# controller.net
KiCad netlist of a schematic drawn in EAGLE
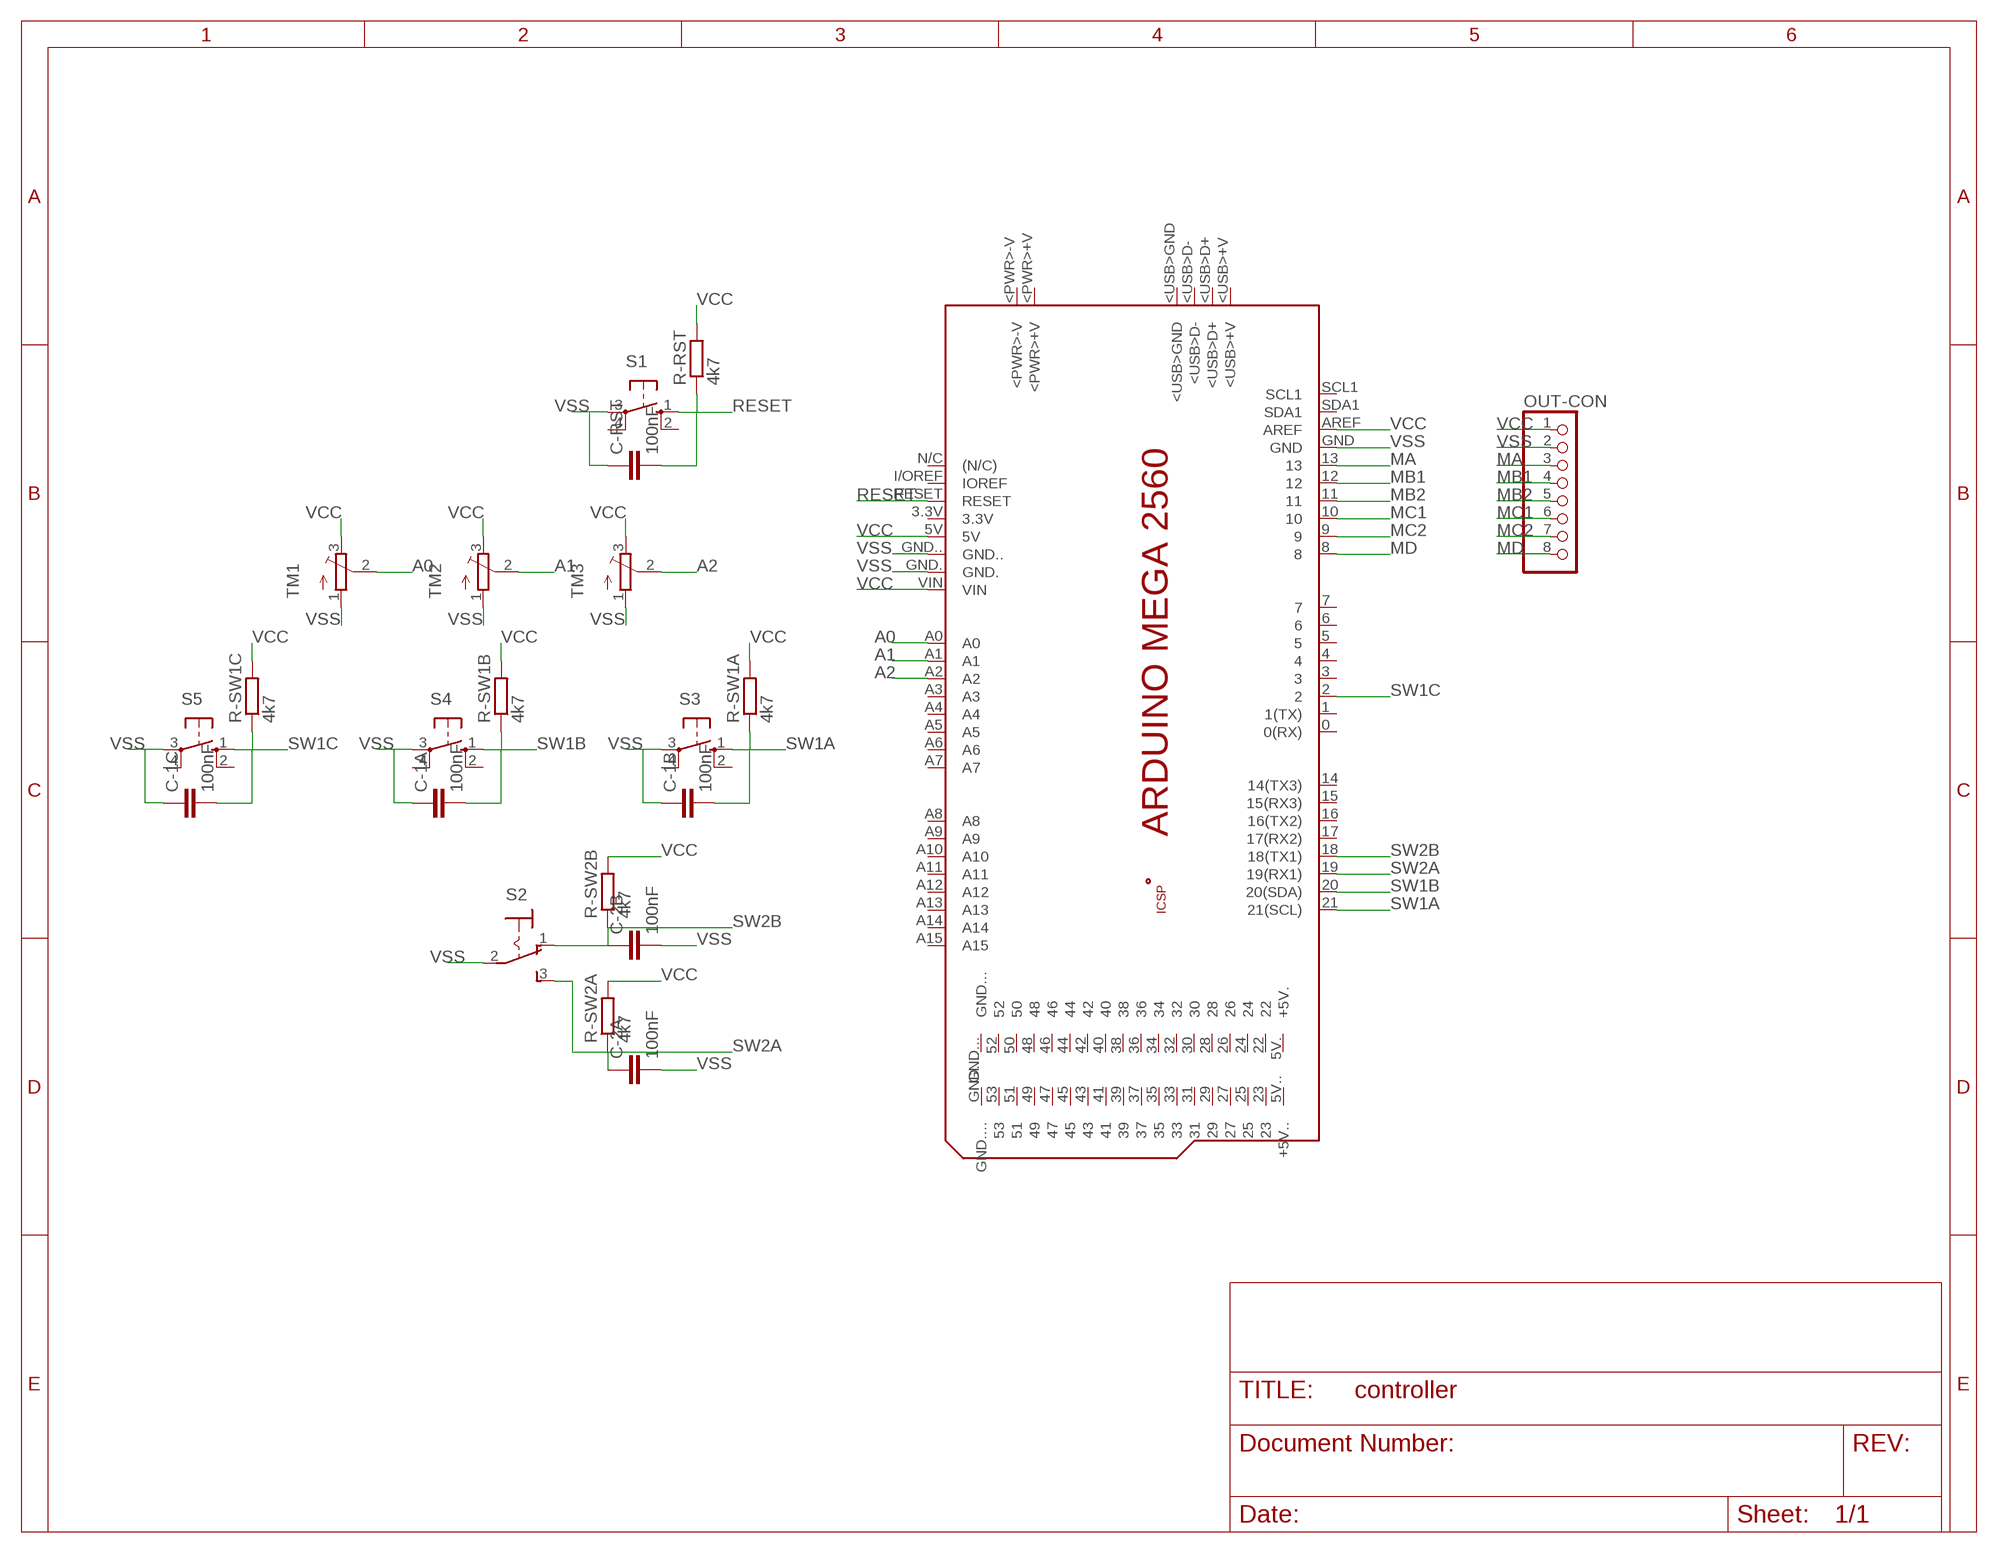
[diagram p0: schematic, sheet 1]

(export (version "E")
  (design (tool "Eeschema 10.0.6"))
  (components
    (comp (ref "C-1A")
      (value "100nF")
      (footprint "eagle-import:C025-024X044")
      (libsource (lib "eagle-import") (part "C-EU025-024X044"))
    )
    (comp (ref "C-1B")
      (value "100nF")
      (footprint "eagle-import:C025-024X044")
      (libsource (lib "eagle-import") (part "C-EU025-024X044"))
    )
    (comp (ref "C-1C")
      (value "100nF")
      (footprint "eagle-import:C025-024X044")
      (libsource (lib "eagle-import") (part "C-EU025-024X044"))
    )
    (comp (ref "C-2A")
      (value "100nF")
      (footprint "eagle-import:C025-024X044")
      (libsource (lib "eagle-import") (part "C-EU025-024X044"))
    )
    (comp (ref "C-2B")
      (value "100nF")
      (footprint "eagle-import:C025-024X044")
      (libsource (lib "eagle-import") (part "C-EU025-024X044"))
    )
    (comp (ref "C-RST")
      (value "100nF")
      (footprint "eagle-import:C025-024X044")
      (libsource (lib "eagle-import") (part "C-EU025-024X044"))
    )
    (comp (ref "OUT-CON")
      (value "PINHD-1X8")
      (footprint "eagle-import:1X08")
      (libsource (lib "eagle-import") (part "PINHD-1X8"))
    )
    (comp (ref "PCB1")
      (value "ARDUINO_MEGA2560")
      (footprint "eagle-import:ARDUINO_MEGA2560")
      (libsource (lib "eagle-import") (part "ARDUINO_MEGA2560"))
    )
    (comp (ref "R-RST")
      (value "4k7")
      (footprint "eagle-import:0204_7")
      (libsource (lib "eagle-import") (part "R-EU_0204/7"))
    )
    (comp (ref "R-SW1A")
      (value "4k7")
      (footprint "eagle-import:0204_7")
      (libsource (lib "eagle-import") (part "R-EU_0204/7"))
    )
    (comp (ref "R-SW1B")
      (value "4k7")
      (footprint "eagle-import:0204_7")
      (libsource (lib "eagle-import") (part "R-EU_0204/7"))
    )
    (comp (ref "R-SW1C")
      (value "4k7")
      (footprint "eagle-import:0204_7")
      (libsource (lib "eagle-import") (part "R-EU_0204/7"))
    )
    (comp (ref "R-SW2A")
      (value "4k7")
      (footprint "eagle-import:0204_7")
      (libsource (lib "eagle-import") (part "R-EU_0204/7"))
    )
    (comp (ref "R-SW2B")
      (value "4k7")
      (footprint "eagle-import:0204_7")
      (libsource (lib "eagle-import") (part "R-EU_0204/7"))
    )
    (comp (ref "S1")
      (value "10-XX")
      (footprint "eagle-import:B3F-10XX")
      (fields (field (name "MPN") "B3F-1000"))
      (libsource (lib "eagle-import") (part "10-XX"))
    )
    (comp (ref "S2")
      (value "M9040P")
      (footprint "eagle-import:M9040P")
      (libsource (lib "eagle-import") (part "M9040P"))
    )
    (comp (ref "S3")
      (value "10-XX")
      (footprint "eagle-import:B3F-10XX")
      (fields (field (name "MPN") "B3F-1000"))
      (libsource (lib "eagle-import") (part "10-XX"))
    )
    (comp (ref "S4")
      (value "10-XX")
      (footprint "eagle-import:B3F-10XX")
      (fields (field (name "MPN") "B3F-1000"))
      (libsource (lib "eagle-import") (part "10-XX"))
    )
    (comp (ref "S5")
      (value "10-XX")
      (footprint "eagle-import:B3F-10XX")
      (fields (field (name "MPN") "B3F-1000"))
      (libsource (lib "eagle-import") (part "10-XX"))
    )
    (comp (ref "TM1")
      (value "TRIMPOT3386")
      (footprint "eagle-import:TRIM-3386")
      (libsource (lib "eagle-import") (part "TRIMPOT3386"))
    )
    (comp (ref "TM2")
      (value "TRIMPOT3386")
      (footprint "eagle-import:TRIM-3386")
      (libsource (lib "eagle-import") (part "TRIMPOT3386"))
    )
    (comp (ref "TM3")
      (value "TRIMPOT3386")
      (footprint "eagle-import:TRIM-3386")
      (libsource (lib "eagle-import") (part "TRIMPOT3386"))
    )
  )
  (nets
    (net (code "1") (name "/A0") (class "Default")
      (node (ref "PCB1") (pin "A0") (pinfunction "A0_A0") (pintype "bidirectional"))
      (node (ref "TM1") (pin "2") (pinfunction "S_2") (pintype "passive"))
    )
    (net (code "2") (name "/A1") (class "Default")
      (node (ref "PCB1") (pin "A1") (pinfunction "A1_A1") (pintype "bidirectional"))
      (node (ref "TM2") (pin "2") (pinfunction "S_2") (pintype "passive"))
    )
    (net (code "3") (name "/A2") (class "Default")
      (node (ref "PCB1") (pin "A2") (pinfunction "A2_A2") (pintype "bidirectional"))
      (node (ref "TM3") (pin "2") (pinfunction "S_2") (pintype "passive"))
    )
    (net (code "4") (name "/MA") (class "Default")
      (node (ref "OUT-CON") (pin "3") (pinfunction "3_3") (pintype "passive"))
      (node (ref "PCB1") (pin "13") (pinfunction "13_13") (pintype "bidirectional"))
    )
    (net (code "5") (name "/MB1") (class "Default")
      (node (ref "OUT-CON") (pin "4") (pinfunction "4_4") (pintype "passive"))
      (node (ref "PCB1") (pin "12") (pinfunction "12_12") (pintype "bidirectional"))
    )
    (net (code "6") (name "/MB2") (class "Default")
      (node (ref "OUT-CON") (pin "5") (pinfunction "5_5") (pintype "passive"))
      (node (ref "PCB1") (pin "11") (pinfunction "11_11") (pintype "bidirectional"))
    )
    (net (code "7") (name "/MC1") (class "Default")
      (node (ref "OUT-CON") (pin "6") (pinfunction "6_6") (pintype "passive"))
      (node (ref "PCB1") (pin "10") (pinfunction "10_10") (pintype "bidirectional"))
    )
    (net (code "8") (name "/MC2") (class "Default")
      (node (ref "OUT-CON") (pin "7") (pinfunction "7_7") (pintype "passive"))
      (node (ref "PCB1") (pin "9") (pinfunction "9_9") (pintype "bidirectional"))
    )
    (net (code "9") (name "/MD") (class "Default")
      (node (ref "OUT-CON") (pin "8") (pinfunction "8_8") (pintype "passive"))
      (node (ref "PCB1") (pin "8") (pinfunction "8_8") (pintype "bidirectional"))
    )
    (net (code "10") (name "/RESET") (class "Default")
      (node (ref "C-RST") (pin "2") (pinfunction "2_2") (pintype "passive"))
      (node (ref "PCB1") (pin "RESET") (pinfunction "RESET_RESET") (pintype "bidirectional"))
      (node (ref "R-RST") (pin "1") (pinfunction "1_1") (pintype "passive"))
      (node (ref "S1") (pin "1") (pinfunction "S_1") (pintype "passive"))
    )
    (net (code "11") (name "/SW1A") (class "Default")
      (node (ref "C-1B") (pin "2") (pinfunction "2_2") (pintype "passive"))
      (node (ref "PCB1") (pin "21") (pinfunction "21(SCL)_21") (pintype "bidirectional"))
      (node (ref "R-SW1A") (pin "1") (pinfunction "1_1") (pintype "passive"))
      (node (ref "S3") (pin "1") (pinfunction "S_1") (pintype "passive"))
    )
    (net (code "12") (name "/SW1B") (class "Default")
      (node (ref "C-1A") (pin "2") (pinfunction "2_2") (pintype "passive"))
      (node (ref "PCB1") (pin "20") (pinfunction "20(SDA)_20") (pintype "bidirectional"))
      (node (ref "R-SW1B") (pin "1") (pinfunction "1_1") (pintype "passive"))
      (node (ref "S4") (pin "1") (pinfunction "S_1") (pintype "passive"))
    )
    (net (code "13") (name "/SW1C") (class "Default")
      (node (ref "C-1C") (pin "2") (pinfunction "2_2") (pintype "passive"))
      (node (ref "PCB1") (pin "2") (pinfunction "2_2") (pintype "bidirectional"))
      (node (ref "R-SW1C") (pin "1") (pinfunction "1_1") (pintype "passive"))
      (node (ref "S5") (pin "1") (pinfunction "S_1") (pintype "passive"))
    )
    (net (code "14") (name "/SW2A") (class "Default")
      (node (ref "C-2A") (pin "1") (pinfunction "1_1") (pintype "passive"))
      (node (ref "PCB1") (pin "19") (pinfunction "19(RX1)_19") (pintype "bidirectional"))
      (node (ref "R-SW2A") (pin "1") (pinfunction "1_1") (pintype "passive"))
      (node (ref "S2") (pin "3") (pinfunction "S_3") (pintype "passive"))
    )
    (net (code "15") (name "/SW2B") (class "Default")
      (node (ref "C-2B") (pin "1") (pinfunction "1_1") (pintype "passive"))
      (node (ref "PCB1") (pin "18") (pinfunction "18(TX1)_18") (pintype "bidirectional"))
      (node (ref "R-SW2B") (pin "1") (pinfunction "1_1") (pintype "passive"))
      (node (ref "S2") (pin "1") (pinfunction "O_1") (pintype "passive"))
    )
    (net (code "16") (name "/VCC") (class "Default")
      (node (ref "OUT-CON") (pin "1") (pinfunction "1_1") (pintype "passive"))
      (node (ref "PCB1") (pin "5V") (pinfunction "5V_5V") (pintype "bidirectional"))
      (node (ref "PCB1") (pin "AREF") (pinfunction "AREF_AREF") (pintype "bidirectional"))
      (node (ref "PCB1") (pin "VIN") (pinfunction "VIN_VIN") (pintype "bidirectional"))
      (node (ref "R-RST") (pin "2") (pinfunction "2_2") (pintype "passive"))
      (node (ref "R-SW1A") (pin "2") (pinfunction "2_2") (pintype "passive"))
      (node (ref "R-SW1B") (pin "2") (pinfunction "2_2") (pintype "passive"))
      (node (ref "R-SW1C") (pin "2") (pinfunction "2_2") (pintype "passive"))
      (node (ref "R-SW2A") (pin "2") (pinfunction "2_2") (pintype "passive"))
      (node (ref "R-SW2B") (pin "2") (pinfunction "2_2") (pintype "passive"))
      (node (ref "TM1") (pin "3") (pinfunction "E_3") (pintype "passive"))
      (node (ref "TM2") (pin "3") (pinfunction "E_3") (pintype "passive"))
      (node (ref "TM3") (pin "3") (pinfunction "E_3") (pintype "passive"))
    )
    (net (code "17") (name "/VSS") (class "Default")
      (node (ref "C-1A") (pin "1") (pinfunction "1_1") (pintype "passive"))
      (node (ref "C-1B") (pin "1") (pinfunction "1_1") (pintype "passive"))
      (node (ref "C-1C") (pin "1") (pinfunction "1_1") (pintype "passive"))
      (node (ref "C-2A") (pin "2") (pinfunction "2_2") (pintype "passive"))
      (node (ref "C-2B") (pin "2") (pinfunction "2_2") (pintype "passive"))
      (node (ref "C-RST") (pin "1") (pinfunction "1_1") (pintype "passive"))
      (node (ref "OUT-CON") (pin "2") (pinfunction "2_2") (pintype "passive"))
      (node (ref "PCB1") (pin "GND") (pinfunction "GND_GND") (pintype "bidirectional"))
      (node (ref "PCB1") (pin "GND.") (pinfunction "GND._GND.") (pintype "bidirectional"))
      (node (ref "PCB1") (pin "GND..") (pinfunction "GND.._GND..") (pintype "bidirectional"))
      (node (ref "S1") (pin "3") (pinfunction "P_3") (pintype "passive"))
      (node (ref "S2") (pin "2") (pinfunction "P_2") (pintype "passive"))
      (node (ref "S3") (pin "3") (pinfunction "P_3") (pintype "passive"))
      (node (ref "S4") (pin "3") (pinfunction "P_3") (pintype "passive"))
      (node (ref "S5") (pin "3") (pinfunction "P_3") (pintype "passive"))
      (node (ref "TM1") (pin "1") (pinfunction "A_1") (pintype "passive"))
      (node (ref "TM2") (pin "1") (pinfunction "A_1") (pintype "passive"))
      (node (ref "TM3") (pin "1") (pinfunction "A_1") (pintype "passive"))
    )
    (net (code "18") (name "unconnected-(PCB1-(N{slash}C)-PadN{slash}C)") (class "Default")
      (node (ref "PCB1") (pin "N/C") (pinfunction "(N/C)_N/C") (pintype "bidirectional"))
    )
    (net (code "19") (name "unconnected-(PCB1-+5V.-Pad5V.)") (class "Default")
      (node (ref "PCB1") (pin "5V.") (pinfunction "+5V._5V.") (pintype "bidirectional"))
    )
    (net (code "20") (name "unconnected-(PCB1-+5V..-Pad5V..)") (class "Default")
      (node (ref "PCB1") (pin "5V..") (pinfunction "+5V.._5V..") (pintype "bidirectional"))
    )
    (net (code "21") (name "unconnected-(PCB1-0(RX)-Pad0)") (class "Default")
      (node (ref "PCB1") (pin "0") (pinfunction "0(RX)_0") (pintype "bidirectional"))
    )
    (net (code "22") (name "unconnected-(PCB1-1(TX)-Pad1)") (class "Default")
      (node (ref "PCB1") (pin "1") (pinfunction "1(TX)_1") (pintype "bidirectional"))
    )
    (net (code "23") (name "unconnected-(PCB1-14(TX3)-Pad14)") (class "Default")
      (node (ref "PCB1") (pin "14") (pinfunction "14(TX3)_14") (pintype "bidirectional"))
    )
    (net (code "24") (name "unconnected-(PCB1-15(RX3)-Pad15)") (class "Default")
      (node (ref "PCB1") (pin "15") (pinfunction "15(RX3)_15") (pintype "bidirectional"))
    )
    (net (code "25") (name "unconnected-(PCB1-16(TX2)-Pad16)") (class "Default")
      (node (ref "PCB1") (pin "16") (pinfunction "16(TX2)_16") (pintype "bidirectional"))
    )
    (net (code "26") (name "unconnected-(PCB1-17(RX2)-Pad17)") (class "Default")
      (node (ref "PCB1") (pin "17") (pinfunction "17(RX2)_17") (pintype "bidirectional"))
    )
    (net (code "27") (name "unconnected-(PCB1-IOREF-PadI{slash}OREF)") (class "Default")
      (node (ref "PCB1") (pin "I/OREF") (pinfunction "IOREF_I/OREF") (pintype "bidirectional"))
    )
    (net (code "28") (name "unconnected-(PCB1-Pad+5V_)") (class "Default")
      (node (ref "PCB1") (pin "+5V_") (pinfunction "+5V__+5V_") (pintype "bidirectional"))
    )
    (net (code "29") (name "unconnected-(PCB1-Pad3)") (class "Default")
      (node (ref "PCB1") (pin "3") (pinfunction "3_3") (pintype "bidirectional"))
    )
    (net (code "30") (name "unconnected-(PCB1-Pad3.3V)") (class "Default")
      (node (ref "PCB1") (pin "3.3V") (pinfunction "3.3V_3.3V") (pintype "bidirectional"))
    )
    (net (code "31") (name "unconnected-(PCB1-Pad4)") (class "Default")
      (node (ref "PCB1") (pin "4") (pinfunction "4_4") (pintype "bidirectional"))
    )
    (net (code "32") (name "unconnected-(PCB1-Pad5)") (class "Default")
      (node (ref "PCB1") (pin "5") (pinfunction "5_5") (pintype "bidirectional"))
    )
    (net (code "33") (name "unconnected-(PCB1-Pad6)") (class "Default")
      (node (ref "PCB1") (pin "6") (pinfunction "6_6") (pintype "bidirectional"))
    )
    (net (code "34") (name "unconnected-(PCB1-Pad7)") (class "Default")
      (node (ref "PCB1") (pin "7") (pinfunction "7_7") (pintype "bidirectional"))
    )
    (net (code "35") (name "unconnected-(PCB1-Pad22)") (class "Default")
      (node (ref "PCB1") (pin "22") (pinfunction "22_22") (pintype "bidirectional"))
    )
    (net (code "36") (name "unconnected-(PCB1-Pad23)") (class "Default")
      (node (ref "PCB1") (pin "23") (pinfunction "23_23") (pintype "bidirectional"))
    )
    (net (code "37") (name "unconnected-(PCB1-Pad24)") (class "Default")
      (node (ref "PCB1") (pin "24") (pinfunction "24_24") (pintype "bidirectional"))
    )
    (net (code "38") (name "unconnected-(PCB1-Pad25)") (class "Default")
      (node (ref "PCB1") (pin "25") (pinfunction "25_25") (pintype "bidirectional"))
    )
    (net (code "39") (name "unconnected-(PCB1-Pad26)") (class "Default")
      (node (ref "PCB1") (pin "26") (pinfunction "26_26") (pintype "bidirectional"))
    )
    (net (code "40") (name "unconnected-(PCB1-Pad27)") (class "Default")
      (node (ref "PCB1") (pin "27") (pinfunction "27_27") (pintype "bidirectional"))
    )
    (net (code "41") (name "unconnected-(PCB1-Pad28)") (class "Default")
      (node (ref "PCB1") (pin "28") (pinfunction "28_28") (pintype "bidirectional"))
    )
    (net (code "42") (name "unconnected-(PCB1-Pad29)") (class "Default")
      (node (ref "PCB1") (pin "29") (pinfunction "29_29") (pintype "bidirectional"))
    )
    (net (code "43") (name "unconnected-(PCB1-Pad30)") (class "Default")
      (node (ref "PCB1") (pin "30") (pinfunction "30_30") (pintype "bidirectional"))
    )
    (net (code "44") (name "unconnected-(PCB1-Pad31)") (class "Default")
      (node (ref "PCB1") (pin "31") (pinfunction "31_31") (pintype "bidirectional"))
    )
    (net (code "45") (name "unconnected-(PCB1-Pad32)") (class "Default")
      (node (ref "PCB1") (pin "32") (pinfunction "32_32") (pintype "bidirectional"))
    )
    (net (code "46") (name "unconnected-(PCB1-Pad33)") (class "Default")
      (node (ref "PCB1") (pin "33") (pinfunction "33_33") (pintype "bidirectional"))
    )
    (net (code "47") (name "unconnected-(PCB1-Pad34)") (class "Default")
      (node (ref "PCB1") (pin "34") (pinfunction "34_34") (pintype "bidirectional"))
    )
    (net (code "48") (name "unconnected-(PCB1-Pad35)") (class "Default")
      (node (ref "PCB1") (pin "35") (pinfunction "35_35") (pintype "bidirectional"))
    )
    (net (code "49") (name "unconnected-(PCB1-Pad36)") (class "Default")
      (node (ref "PCB1") (pin "36") (pinfunction "36_36") (pintype "bidirectional"))
    )
    (net (code "50") (name "unconnected-(PCB1-Pad37)") (class "Default")
      (node (ref "PCB1") (pin "37") (pinfunction "37_37") (pintype "bidirectional"))
    )
    (net (code "51") (name "unconnected-(PCB1-Pad38)") (class "Default")
      (node (ref "PCB1") (pin "38") (pinfunction "38_38") (pintype "bidirectional"))
    )
    (net (code "52") (name "unconnected-(PCB1-Pad39)") (class "Default")
      (node (ref "PCB1") (pin "39") (pinfunction "39_39") (pintype "bidirectional"))
    )
    (net (code "53") (name "unconnected-(PCB1-Pad40)") (class "Default")
      (node (ref "PCB1") (pin "40") (pinfunction "40_40") (pintype "bidirectional"))
    )
    (net (code "54") (name "unconnected-(PCB1-Pad41)") (class "Default")
      (node (ref "PCB1") (pin "41") (pinfunction "41_41") (pintype "bidirectional"))
    )
    (net (code "55") (name "unconnected-(PCB1-Pad42)") (class "Default")
      (node (ref "PCB1") (pin "42") (pinfunction "42_42") (pintype "bidirectional"))
    )
    (net (code "56") (name "unconnected-(PCB1-Pad43)") (class "Default")
      (node (ref "PCB1") (pin "43") (pinfunction "43_43") (pintype "bidirectional"))
    )
    (net (code "57") (name "unconnected-(PCB1-Pad44)") (class "Default")
      (node (ref "PCB1") (pin "44") (pinfunction "44_44") (pintype "bidirectional"))
    )
    (net (code "58") (name "unconnected-(PCB1-Pad45)") (class "Default")
      (node (ref "PCB1") (pin "45") (pinfunction "45_45") (pintype "bidirectional"))
    )
    (net (code "59") (name "unconnected-(PCB1-Pad46)") (class "Default")
      (node (ref "PCB1") (pin "46") (pinfunction "46_46") (pintype "bidirectional"))
    )
    (net (code "60") (name "unconnected-(PCB1-Pad47)") (class "Default")
      (node (ref "PCB1") (pin "47") (pinfunction "47_47") (pintype "bidirectional"))
    )
    (net (code "61") (name "unconnected-(PCB1-Pad48)") (class "Default")
      (node (ref "PCB1") (pin "48") (pinfunction "48_48") (pintype "bidirectional"))
    )
    (net (code "62") (name "unconnected-(PCB1-Pad49)") (class "Default")
      (node (ref "PCB1") (pin "49") (pinfunction "49_49") (pintype "bidirectional"))
    )
    (net (code "63") (name "unconnected-(PCB1-Pad50)") (class "Default")
      (node (ref "PCB1") (pin "50") (pinfunction "50_50") (pintype "bidirectional"))
    )
    (net (code "64") (name "unconnected-(PCB1-Pad51)") (class "Default")
      (node (ref "PCB1") (pin "51") (pinfunction "51_51") (pintype "bidirectional"))
    )
    (net (code "65") (name "unconnected-(PCB1-Pad52)") (class "Default")
      (node (ref "PCB1") (pin "52") (pinfunction "52_52") (pintype "bidirectional"))
    )
    (net (code "66") (name "unconnected-(PCB1-Pad53)") (class "Default")
      (node (ref "PCB1") (pin "53") (pinfunction "53_53") (pintype "bidirectional"))
    )
    (net (code "67") (name "unconnected-(PCB1-Pad<PWR>+V)") (class "Default")
      (node (ref "PCB1") (pin "<PWR>+V") (pinfunction "<PWR>+V_<PWR>+V") (pintype "no_connect"))
    )
    (net (code "68") (name "unconnected-(PCB1-Pad<PWR>-V)") (class "Default")
      (node (ref "PCB1") (pin "<PWR>-V") (pinfunction "<PWR>-V_<PWR>-V") (pintype "no_connect"))
    )
    (net (code "69") (name "unconnected-(PCB1-Pad<USB>+V)") (class "Default")
      (node (ref "PCB1") (pin "<USB>+V") (pinfunction "<USB>+V_<USB>+V") (pintype "no_connect"))
    )
    (net (code "70") (name "unconnected-(PCB1-Pad<USB>D+)") (class "Default")
      (node (ref "PCB1") (pin "<USB>D+") (pinfunction "<USB>D+_<USB>D+") (pintype "no_connect"))
    )
    (net (code "71") (name "unconnected-(PCB1-Pad<USB>D-)") (class "Default")
      (node (ref "PCB1") (pin "<USB>D-") (pinfunction "<USB>D-_<USB>D-") (pintype "no_connect"))
    )
    (net (code "72") (name "unconnected-(PCB1-Pad<USB>GND)") (class "Default")
      (node (ref "PCB1") (pin "<USB>GND") (pinfunction "<USB>GND_<USB>GND") (pintype "no_connect"))
    )
    (net (code "73") (name "unconnected-(PCB1-PadA3)") (class "Default")
      (node (ref "PCB1") (pin "A3") (pinfunction "A3_A3") (pintype "bidirectional"))
    )
    (net (code "74") (name "unconnected-(PCB1-PadA4)") (class "Default")
      (node (ref "PCB1") (pin "A4") (pinfunction "A4_A4") (pintype "bidirectional"))
    )
    (net (code "75") (name "unconnected-(PCB1-PadA5)") (class "Default")
      (node (ref "PCB1") (pin "A5") (pinfunction "A5_A5") (pintype "bidirectional"))
    )
    (net (code "76") (name "unconnected-(PCB1-PadA6)") (class "Default")
      (node (ref "PCB1") (pin "A6") (pinfunction "A6_A6") (pintype "bidirectional"))
    )
    (net (code "77") (name "unconnected-(PCB1-PadA7)") (class "Default")
      (node (ref "PCB1") (pin "A7") (pinfunction "A7_A7") (pintype "bidirectional"))
    )
    (net (code "78") (name "unconnected-(PCB1-PadA8)") (class "Default")
      (node (ref "PCB1") (pin "A8") (pinfunction "A8_A8") (pintype "bidirectional"))
    )
    (net (code "79") (name "unconnected-(PCB1-PadA9)") (class "Default")
      (node (ref "PCB1") (pin "A9") (pinfunction "A9_A9") (pintype "bidirectional"))
    )
    (net (code "80") (name "unconnected-(PCB1-PadA10)") (class "Default")
      (node (ref "PCB1") (pin "A10") (pinfunction "A10_A10") (pintype "bidirectional"))
    )
    (net (code "81") (name "unconnected-(PCB1-PadA11)") (class "Default")
      (node (ref "PCB1") (pin "A11") (pinfunction "A11_A11") (pintype "bidirectional"))
    )
    (net (code "82") (name "unconnected-(PCB1-PadA12)") (class "Default")
      (node (ref "PCB1") (pin "A12") (pinfunction "A12_A12") (pintype "bidirectional"))
    )
    (net (code "83") (name "unconnected-(PCB1-PadA13)") (class "Default")
      (node (ref "PCB1") (pin "A13") (pinfunction "A13_A13") (pintype "bidirectional"))
    )
    (net (code "84") (name "unconnected-(PCB1-PadA14)") (class "Default")
      (node (ref "PCB1") (pin "A14") (pinfunction "A14_A14") (pintype "bidirectional"))
    )
    (net (code "85") (name "unconnected-(PCB1-PadA15)") (class "Default")
      (node (ref "PCB1") (pin "A15") (pinfunction "A15_A15") (pintype "bidirectional"))
    )
    (net (code "86") (name "unconnected-(PCB1-PadGND...)") (class "Default")
      (node (ref "PCB1") (pin "GND...") (pinfunction "GND..._GND...") (pintype "bidirectional"))
    )
    (net (code "87") (name "unconnected-(PCB1-PadGND....)") (class "Default")
      (node (ref "PCB1") (pin "GND....") (pinfunction "GND...._GND....") (pintype "bidirectional"))
    )
    (net (code "88") (name "unconnected-(PCB1-PadGND__)") (class "Default")
      (node (ref "PCB1") (pin "GND__") (pinfunction "GND___GND__") (pintype "bidirectional"))
    )
    (net (code "89") (name "unconnected-(PCB1-PadMISO)") (class "Default")
      (node (ref "PCB1") (pin "MISO") (pinfunction "MISO_MISO") (pintype "bidirectional"))
    )
    (net (code "90") (name "unconnected-(PCB1-PadMOSI)") (class "Default")
      (node (ref "PCB1") (pin "MOSI") (pinfunction "MOSI_MOSI") (pintype "bidirectional"))
    )
    (net (code "91") (name "unconnected-(PCB1-PadRESET.)") (class "Default")
      (node (ref "PCB1") (pin "RESET.") (pinfunction "RESET._RESET.") (pintype "bidirectional"))
    )
    (net (code "92") (name "unconnected-(PCB1-PadSCK)") (class "Default")
      (node (ref "PCB1") (pin "SCK") (pinfunction "SCK_SCK") (pintype "bidirectional"))
    )
    (net (code "93") (name "unconnected-(PCB1-PadSCL1)") (class "Default")
      (node (ref "PCB1") (pin "SCL1") (pinfunction "SCL1_SCL1") (pintype "bidirectional"))
    )
    (net (code "94") (name "unconnected-(PCB1-PadSDA1)") (class "Default")
      (node (ref "PCB1") (pin "SDA1") (pinfunction "SDA1_SDA1") (pintype "bidirectional"))
    )
    (net (code "95") (name "unconnected-(S1-P1-Pad4)") (class "Default")
      (node (ref "S1") (pin "4") (pinfunction "P1_4") (pintype "passive"))
    )
    (net (code "96") (name "unconnected-(S1-S1-Pad2)") (class "Default")
      (node (ref "S1") (pin "2") (pinfunction "S1_2") (pintype "passive"))
    )
    (net (code "97") (name "unconnected-(S3-P1-Pad4)") (class "Default")
      (node (ref "S3") (pin "4") (pinfunction "P1_4") (pintype "passive"))
    )
    (net (code "98") (name "unconnected-(S3-S1-Pad2)") (class "Default")
      (node (ref "S3") (pin "2") (pinfunction "S1_2") (pintype "passive"))
    )
    (net (code "99") (name "unconnected-(S4-P1-Pad4)") (class "Default")
      (node (ref "S4") (pin "4") (pinfunction "P1_4") (pintype "passive"))
    )
    (net (code "100") (name "unconnected-(S4-S1-Pad2)") (class "Default")
      (node (ref "S4") (pin "2") (pinfunction "S1_2") (pintype "passive"))
    )
    (net (code "101") (name "unconnected-(S5-P1-Pad4)") (class "Default")
      (node (ref "S5") (pin "4") (pinfunction "P1_4") (pintype "passive"))
    )
    (net (code "102") (name "unconnected-(S5-S1-Pad2)") (class "Default")
      (node (ref "S5") (pin "2") (pinfunction "S1_2") (pintype "passive"))
    )
  )
)
